# Power_Controller_In_ROV_V1_0.net
KiCad netlist of a schematic drawn in Altium Designer
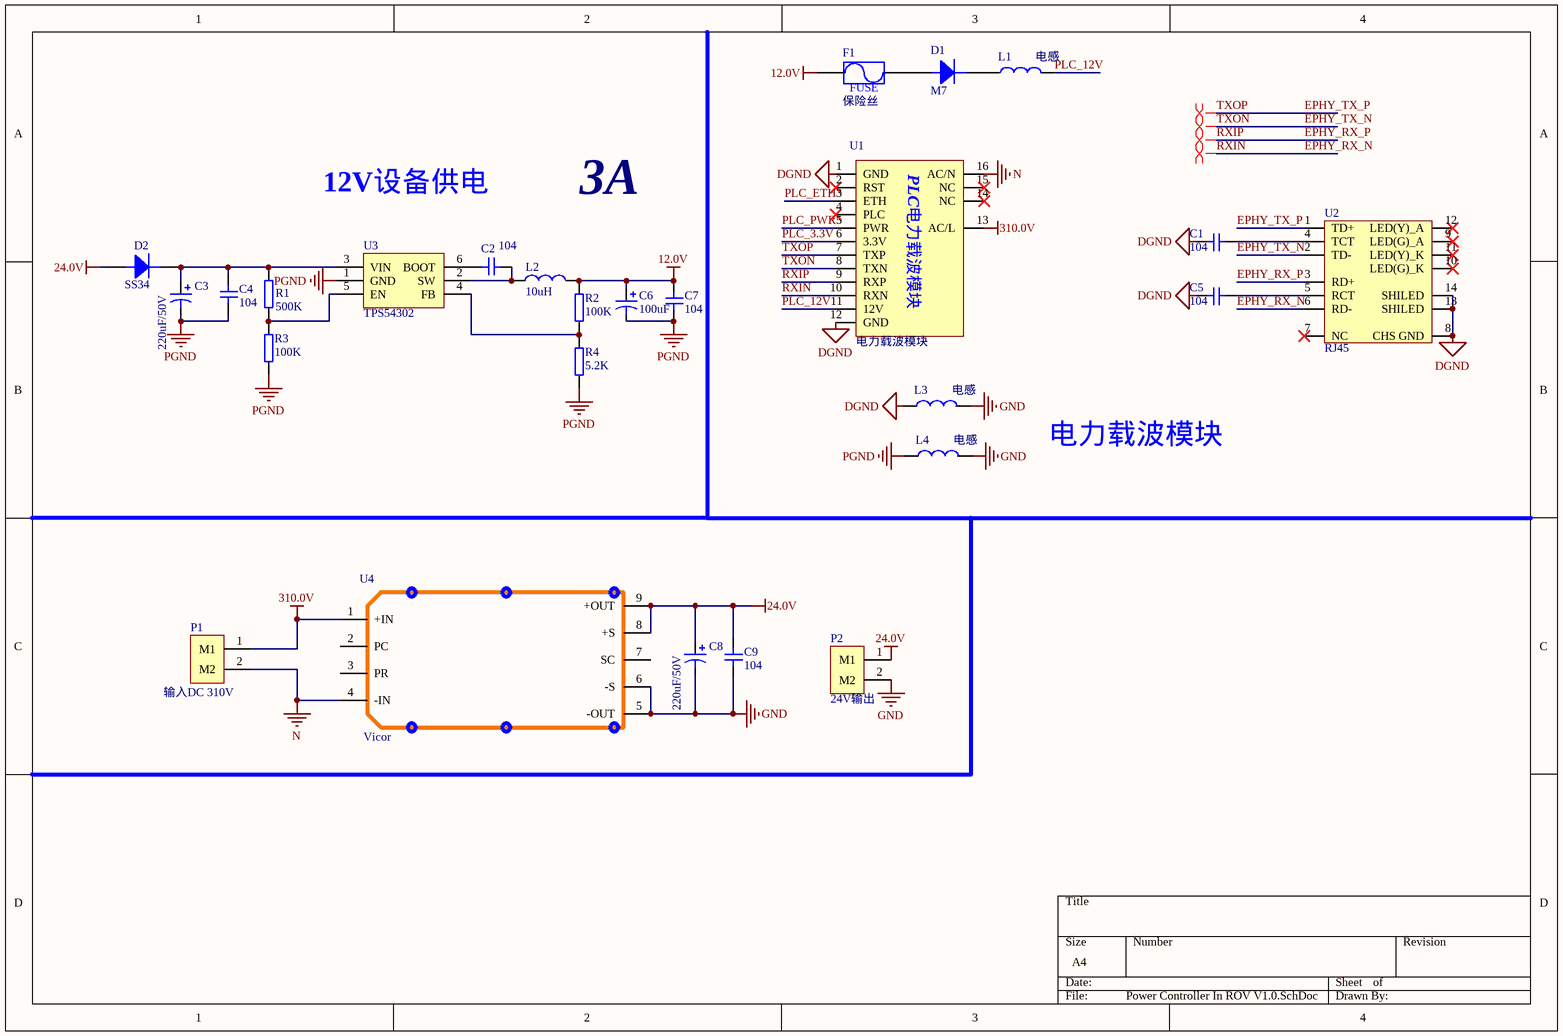
[diagram p0: Power Controller In ROV V1.0.SchDoc]

(export (version "E")
  (design (tool "Eeschema 10.0.6"))
  (components
    (comp (ref "C1")
      (value "104")
      (footprint "0805C")
      (description "无极贴片电容")
      (libsource (lib "集大电协1.1.2") (part "Cap1"))
    )
    (comp (ref "C2")
      (value "104")
      (footprint "0805C")
      (description "无极贴片电容")
      (libsource (lib "集大电协1.5") (part "Cap1"))
    )
    (comp (ref "C3")
      (value "220uF/50V")
      (footprint "RB.1.2")
      (description "直插极性电容")
      (libsource (lib "集大电协1.5") (part "Cap3"))
    )
    (comp (ref "C4")
      (value "104")
      (footprint "0805C")
      (description "无极贴片电容")
      (libsource (lib "集大电协1.5") (part "Cap1"))
    )
    (comp (ref "C5")
      (value "104")
      (footprint "0805C")
      (description "无极贴片电容")
      (libsource (lib "集大电协1.1.2") (part "Cap1"))
    )
    (comp (ref "C6")
      (value "100uF")
      (footprint "TAJ-C")
      (description "极性贴片电容")
      (libsource (lib "集大电协1.5") (part "Pol Cap"))
    )
    (comp (ref "C7")
      (value "104")
      (footprint "0805C")
      (description "无极贴片电容")
      (libsource (lib "集大电协1.5") (part "Cap1"))
    )
    (comp (ref "C8")
      (value "220uF/50V")
      (footprint "RB.2.4")
      (description "直插极性电容")
      (libsource (lib "集大电协1.5") (part "Cap3"))
    )
    (comp (ref "C9")
      (value "104")
      (footprint "0805C")
      (description "无极贴片电容")
      (libsource (lib "集大电协1.5") (part "Cap1"))
    )
    (comp (ref "D1")
      (value "M7")
      (footprint "SMA/DO-214AC")
      (description "二极管")
      (libsource (lib "集大电协1.5") (part "Diode"))
    )
    (comp (ref "D2")
      (value "SS34")
      (footprint "SMA/DO-214AC")
      (description "二极管")
      (libsource (lib "集大电协1.5") (part "Diode"))
    )
    (comp (ref "F1") (value "保险丝") (footprint "FUSE-1206") (libsource (lib "集大电协1.2") (part "Fuse")))
    (comp (ref "L1") (value "电感") (footprint "1206L") (libsource (lib "集大电协1.5") (part "L")))
    (comp (ref "L2")
      (value "10uH")
      (footprint "电感")
      (description "电感")
      (libsource (lib "集大电协1.5") (part "L"))
    )
    (comp (ref "L3") (value "电感") (footprint "1206L") (libsource (lib "集大电协1.5") (part "L")))
    (comp (ref "L4") (value "电感") (footprint "1206L") (libsource (lib "集大电协1.5") (part "L")))
    (comp (ref "P1")
      (value "输入DC 310V")
      (footprint "XT60-F")
      (description "2PIN")
      (libsource (lib "集大电协1.5(1)") (part "接线端子-2PIN"))
    )
    (comp (ref "P2")
      (value "24V输出")
      (footprint "XT60-F")
      (description "2PIN")
      (libsource (lib "集大电协1.5(1)") (part "接线端子-2PIN"))
    )
    (comp (ref "R1")
      (value "500K")
      (footprint "0805R")
      (description "电阻")
      (libsource (lib "集大电协1.5") (part "Res"))
    )
    (comp (ref "R2")
      (value "100K")
      (footprint "0805R")
      (description "电阻")
      (libsource (lib "集大电协1.5") (part "Res"))
    )
    (comp (ref "R3")
      (value "100K")
      (footprint "0805R")
      (description "电阻")
      (libsource (lib "集大电协1.5") (part "Res"))
    )
    (comp (ref "R4")
      (value "5.2K")
      (footprint "0805R")
      (description "电阻")
      (libsource (lib "集大电协1.5") (part "Res"))
    )
    (comp (ref "U1")
      (value "电力载波模块")
      (footprint "电力载波模块6410")
      (libsource (lib "集大电协1.2") (part "电力载波模块6410"))
    )
    (comp (ref "U2") (value "RJ45") (footprint "RJ45") (libsource (lib "集大电协1.2") (part "RJ45")))
    (comp (ref "U3") (value "TPS54302") (footprint "SOT23-6") (libsource (lib "集大电协1.5") (part "TPS54302")))
    (comp (ref "U4")
      (value "Vicor")
      (footprint "vicor")
      (libsource (lib "集大电协1.5(1)") (part "滨达模块（220V--24V）"))
    )
  )
  (nets
    (net (code "1") (name "/EPHY_RX_N") (class "Default")
      (node (ref "U1") (pin "10") (pinfunction "RXN_10") (pintype "passive"))
      (node (ref "U2") (pin "6") (pinfunction "RD-_6") (pintype "passive"))
    )
    (net (code "2") (name "/EPHY_RX_P") (class "Default")
      (node (ref "U1") (pin "9") (pinfunction "RXP_9") (pintype "passive"))
      (node (ref "U2") (pin "3") (pinfunction "RD+_3") (pintype "passive"))
    )
    (net (code "3") (name "/EPHY_TX_N") (class "Default")
      (node (ref "U1") (pin "8") (pinfunction "TXN_8") (pintype "passive"))
      (node (ref "U2") (pin "2") (pinfunction "TD-_2") (pintype "passive"))
    )
    (net (code "4") (name "/EPHY_TX_P") (class "Default")
      (node (ref "U1") (pin "7") (pinfunction "TXP_7") (pintype "passive"))
      (node (ref "U2") (pin "1") (pinfunction "TD+_1") (pintype "passive"))
    )
    (net (code "5") (name "/PLC_3.3V") (class "Default")
      (node (ref "U1") (pin "6") (pinfunction "3.3V_6") (pintype "passive"))
    )
    (net (code "6") (name "/PLC_12V") (class "Default")
      (node (ref "L1") (pin "2") (pinfunction "2_2") (pintype "passive"))
      (node (ref "U1") (pin "11") (pinfunction "12V_11") (pintype "passive"))
    )
    (net (code "7") (name "/PLC_ETH") (class "Default")
      (node (ref "U1") (pin "3") (pinfunction "ETH_3") (pintype "passive"))
    )
    (net (code "8") (name "/PLC_PWR") (class "Default")
      (node (ref "U1") (pin "5") (pinfunction "PWR_5") (pintype "passive"))
    )
    (net (code "9") (name "12.0V") (class "Default")
      (node (ref "C6") (pin "1") (pinfunction "1_1") (pintype "passive"))
      (node (ref "C7") (pin "2") (pinfunction "2_2") (pintype "passive"))
      (node (ref "F1") (pin "1") (pinfunction "1_1") (pintype "passive"))
      (node (ref "L2") (pin "2") (pinfunction "2_2") (pintype "passive"))
      (node (ref "R2") (pin "2") (pinfunction "2_2") (pintype "passive"))
    )
    (net (code "10") (name "24.0V") (class "Default")
      (node (ref "C8") (pin "1") (pinfunction "1_1") (pintype "passive"))
      (node (ref "C9") (pin "2") (pinfunction "2_2") (pintype "passive"))
      (node (ref "D2") (pin "1") (pintype "passive"))
      (node (ref "P2") (pin "1") (pinfunction "M1_1") (pintype "passive"))
      (node (ref "U4") (pin "8") (pinfunction "+S_8") (pintype "passive"))
      (node (ref "U4") (pin "9") (pinfunction "+OUT_9") (pintype "passive"))
    )
    (net (code "11") (name "310.0V") (class "Default")
      (node (ref "P1") (pin "1") (pinfunction "M1_1") (pintype "passive"))
      (node (ref "U1") (pin "13") (pinfunction "AC/L_13") (pintype "passive"))
      (node (ref "U4") (pin "1") (pinfunction "+IN_1") (pintype "passive"))
    )
    (net (code "12") (name "DGND") (class "Default")
      (node (ref "C1") (pin "1") (pinfunction "1_1") (pintype "passive"))
      (node (ref "C5") (pin "1") (pinfunction "1_1") (pintype "passive"))
      (node (ref "L3") (pin "1") (pinfunction "1_1") (pintype "passive"))
      (node (ref "U1") (pin "1") (pinfunction "GND_1") (pintype "passive"))
      (node (ref "U1") (pin "12") (pinfunction "GND_12") (pintype "passive"))
      (node (ref "U2") (pin "13") (pinfunction "SHILED_13") (pintype "passive"))
      (node (ref "U2") (pin "14") (pinfunction "SHILED_14") (pintype "passive"))
      (node (ref "U2") (pin "8") (pinfunction "CHS_GND_8") (pintype "passive"))
    )
    (net (code "13") (name "GND") (class "Default")
      (node (ref "C8") (pin "2") (pinfunction "2_2") (pintype "passive"))
      (node (ref "C9") (pin "1") (pinfunction "1_1") (pintype "passive"))
      (node (ref "L3") (pin "2") (pinfunction "2_2") (pintype "passive"))
      (node (ref "L4") (pin "2") (pinfunction "2_2") (pintype "passive"))
      (node (ref "P2") (pin "2") (pinfunction "M2_2") (pintype "passive"))
      (node (ref "U4") (pin "5") (pinfunction "-OUT_5") (pintype "passive"))
      (node (ref "U4") (pin "6") (pinfunction "-S_6") (pintype "passive"))
    )
    (net (code "14") (name "N") (class "Default")
      (node (ref "P1") (pin "2") (pinfunction "M2_2") (pintype "passive"))
      (node (ref "U1") (pin "16") (pinfunction "AC/N_16") (pintype "passive"))
      (node (ref "U4") (pin "4") (pinfunction "-IN_4") (pintype "passive"))
    )
    (net (code "15") (name "Net-(D1-Pad1)") (class "Default")
      (node (ref "D1") (pin "1") (pintype "passive"))
      (node (ref "F1") (pin "2") (pinfunction "2_2") (pintype "passive"))
    )
    (net (code "16") (name "Net-(D1-Pad2)") (class "Default")
      (node (ref "D1") (pin "2") (pinfunction "2_2") (pintype "passive"))
      (node (ref "L1") (pin "1") (pinfunction "1_1") (pintype "passive"))
    )
    (net (code "17") (name "Net-(U2-RCT)") (class "Default")
      (node (ref "C5") (pin "2") (pinfunction "2_2") (pintype "passive"))
      (node (ref "U2") (pin "5") (pinfunction "RCT_5") (pintype "passive"))
    )
    (net (code "18") (name "Net-(U2-TCT)") (class "Default")
      (node (ref "C1") (pin "2") (pinfunction "2_2") (pintype "passive"))
      (node (ref "U2") (pin "4") (pinfunction "TCT_4") (pintype "passive"))
    )
    (net (code "19") (name "Net-(U3-BOOT)") (class "Default")
      (node (ref "C2") (pin "2") (pinfunction "2_2") (pintype "passive"))
      (node (ref "U3") (pin "6") (pinfunction "BOOT_6") (pintype "passive"))
    )
    (net (code "20") (name "Net-(U3-EN)") (class "Default")
      (node (ref "R1") (pin "1") (pinfunction "1_1") (pintype "passive"))
      (node (ref "R3") (pin "2") (pinfunction "2_2") (pintype "passive"))
      (node (ref "U3") (pin "5") (pinfunction "EN_5") (pintype "passive"))
    )
    (net (code "21") (name "Net-(U3-FB)") (class "Default")
      (node (ref "R2") (pin "1") (pinfunction "1_1") (pintype "passive"))
      (node (ref "R4") (pin "2") (pinfunction "2_2") (pintype "passive"))
      (node (ref "U3") (pin "4") (pinfunction "FB_4") (pintype "passive"))
    )
    (net (code "22") (name "Net-(U3-SW)") (class "Default")
      (node (ref "C2") (pin "1") (pinfunction "1_1") (pintype "passive"))
      (node (ref "L2") (pin "1") (pinfunction "1_1") (pintype "passive"))
      (node (ref "U3") (pin "2") (pinfunction "SW_2") (pintype "passive"))
    )
    (net (code "23") (name "Net-(U3-VIN)") (class "Default")
      (node (ref "C3") (pin "1") (pinfunction "1_1") (pintype "passive"))
      (node (ref "C4") (pin "2") (pinfunction "2_2") (pintype "passive"))
      (node (ref "D2") (pin "2") (pinfunction "2_2") (pintype "passive"))
      (node (ref "R1") (pin "2") (pinfunction "2_2") (pintype "passive"))
      (node (ref "U3") (pin "3") (pinfunction "VIN_3") (pintype "passive"))
    )
    (net (code "24") (name "PGND") (class "Default")
      (node (ref "C3") (pin "2") (pinfunction "2_2") (pintype "passive"))
      (node (ref "C4") (pin "1") (pinfunction "1_1") (pintype "passive"))
      (node (ref "C6") (pin "2") (pinfunction "2_2") (pintype "passive"))
      (node (ref "C7") (pin "1") (pinfunction "1_1") (pintype "passive"))
      (node (ref "L4") (pin "1") (pinfunction "1_1") (pintype "passive"))
      (node (ref "R3") (pin "1") (pinfunction "1_1") (pintype "passive"))
      (node (ref "R4") (pin "1") (pinfunction "1_1") (pintype "passive"))
      (node (ref "U3") (pin "1") (pinfunction "GND_1") (pintype "passive"))
    )
    (net (code "25") (name "unconnected-(U1-NC-Pad14)") (class "Default")
      (node (ref "U1") (pin "14") (pinfunction "NC_14") (pintype "passive+no_connect"))
    )
    (net (code "26") (name "unconnected-(U1-NC-Pad15)") (class "Default")
      (node (ref "U1") (pin "15") (pinfunction "NC_15") (pintype "passive+no_connect"))
    )
    (net (code "27") (name "unconnected-(U1-PLC-Pad4)") (class "Default")
      (node (ref "U1") (pin "4") (pinfunction "PLC_4") (pintype "passive+no_connect"))
    )
    (net (code "28") (name "unconnected-(U1-RST-Pad2)") (class "Default")
      (node (ref "U1") (pin "2") (pinfunction "RST_2") (pintype "passive+no_connect"))
    )
    (net (code "29") (name "unconnected-(U2-LED(G)_A-Pad9)") (class "Default")
      (node (ref "U2") (pin "9") (pinfunction "LED(G)_A_9") (pintype "passive+no_connect"))
    )
    (net (code "30") (name "unconnected-(U2-LED(G)_K-Pad10)") (class "Default")
      (node (ref "U2") (pin "10") (pinfunction "LED(G)_K_10") (pintype "passive+no_connect"))
    )
    (net (code "31") (name "unconnected-(U2-LED(Y)_A-Pad12)") (class "Default")
      (node (ref "U2") (pin "12") (pinfunction "LED(Y)_A_12") (pintype "passive+no_connect"))
    )
    (net (code "32") (name "unconnected-(U2-LED(Y)_K-Pad11)") (class "Default")
      (node (ref "U2") (pin "11") (pinfunction "LED(Y)_K_11") (pintype "passive+no_connect"))
    )
    (net (code "33") (name "unconnected-(U2-NC-Pad7)") (class "Default")
      (node (ref "U2") (pin "7") (pinfunction "NC_7") (pintype "passive+no_connect"))
    )
    (net (code "34") (name "unconnected-(U4-PC-Pad2)") (class "Default")
      (node (ref "U4") (pin "2") (pinfunction "PC_2") (pintype "passive"))
    )
    (net (code "35") (name "unconnected-(U4-PR-Pad3)") (class "Default")
      (node (ref "U4") (pin "3") (pinfunction "PR_3") (pintype "passive"))
    )
    (net (code "36") (name "unconnected-(U4-SC-Pad7)") (class "Default")
      (node (ref "U4") (pin "7") (pinfunction "SC_7") (pintype "passive"))
    )
  )
)
